# zdoks.net
KiCad netlist of a schematic drawn in Altium Designer
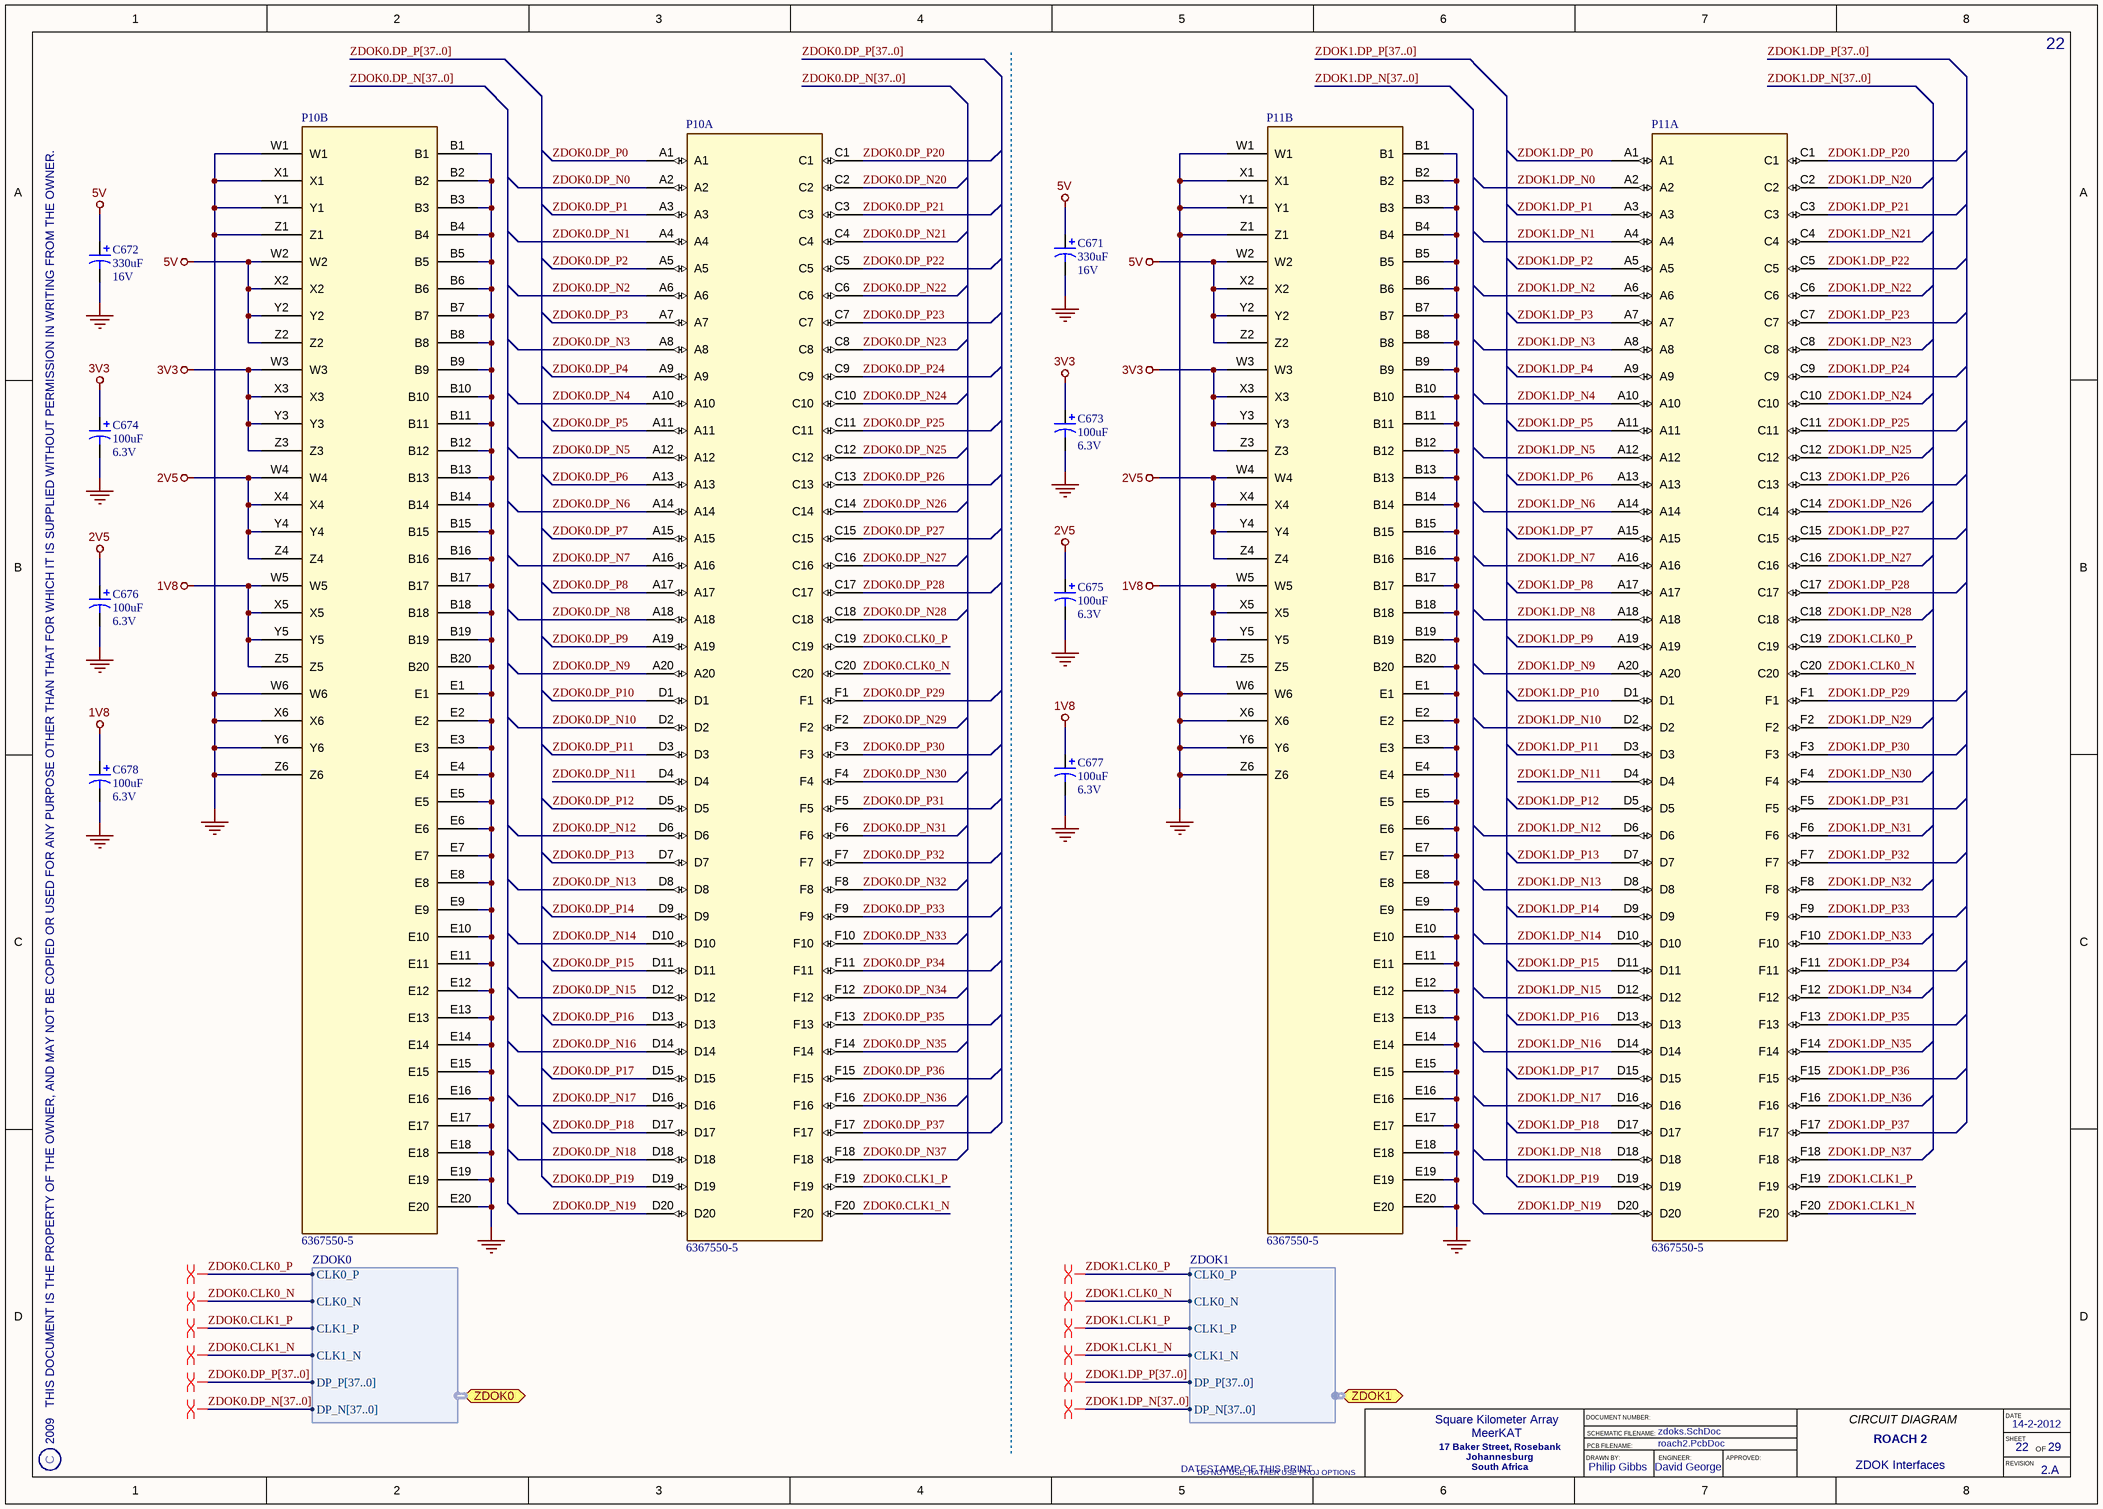
[diagram p0: zdoks.SchDoc]

(export (version "E")
  (design (tool "Eeschema 10.0.6"))
  (components
    (comp (ref "C671")
      (value "330uF")
      (footprint "CAPMP7263X380L")
      (description "330uF, Solid Tantalum Chip Capacitor")
      (fields
        (field (name "RATING") "16V")
        (field (name "MANUFACTURER") "VISHAY")
        (field (name "PARTNUM") "594D337X0016R2T")
      )
      (libsource (lib "altium_db") (part "CapPol"))
    )
    (comp (ref "C672")
      (value "330uF")
      (footprint "CAPMP7263X380L")
      (description "330uF, Solid Tantalum Chip Capacitor")
      (fields
        (field (name "RATING") "16V")
        (field (name "MANUFACTURER") "VISHAY")
        (field (name "PARTNUM") "594D337X0016R2T")
      )
      (libsource (lib "altium_db") (part "CapPol"))
    )
    (comp (ref "C673")
      (value "100uF")
      (footprint "CAPMP3528X210L")
      (description "100uF, Low ESR, Tantalum Capacitor")
      (fields
        (field (name "RATING") "6.3V")
        (field (name "MANUFACTURER") "AVX")
        (field (name "PARTNUM") "TPSB107M006R0200")
      )
      (libsource (lib "altium_db") (part "CapPol"))
    )
    (comp (ref "C674")
      (value "100uF")
      (footprint "CAPMP3528X210L")
      (description "100uF, Low ESR, Tantalum Capacitor")
      (fields
        (field (name "RATING") "6.3V")
        (field (name "MANUFACTURER") "AVX")
        (field (name "PARTNUM") "TPSB107M006R0200")
      )
      (libsource (lib "altium_db") (part "CapPol"))
    )
    (comp (ref "C675")
      (value "100uF")
      (footprint "CAPMP3528X210L")
      (description "100uF, Low ESR, Tantalum Capacitor")
      (fields
        (field (name "RATING") "6.3V")
        (field (name "MANUFACTURER") "AVX")
        (field (name "PARTNUM") "TPSB107M006R0200")
      )
      (libsource (lib "altium_db") (part "CapPol"))
    )
    (comp (ref "C676")
      (value "100uF")
      (footprint "CAPMP3528X210L")
      (description "100uF, Low ESR, Tantalum Capacitor")
      (fields
        (field (name "RATING") "6.3V")
        (field (name "MANUFACTURER") "AVX")
        (field (name "PARTNUM") "TPSB107M006R0200")
      )
      (libsource (lib "altium_db") (part "CapPol"))
    )
    (comp (ref "C677")
      (value "100uF")
      (footprint "CAPMP3528X210L")
      (description "100uF, Low ESR, Tantalum Capacitor")
      (fields
        (field (name "RATING") "6.3V")
        (field (name "MANUFACTURER") "AVX")
        (field (name "PARTNUM") "TPSB107M006R0200")
      )
      (libsource (lib "altium_db") (part "CapPol"))
    )
    (comp (ref "C678")
      (value "100uF")
      (footprint "CAPMP3528X210L")
      (description "100uF, Low ESR, Tantalum Capacitor")
      (fields
        (field (name "RATING") "6.3V")
        (field (name "MANUFACTURER") "AVX")
        (field (name "PARTNUM") "TPSB107M006R0200")
      )
      (libsource (lib "altium_db") (part "CapPol"))
    )
    (comp (ref "P10")
      (value "6367550-5")
      (footprint "TYCO_6367550-5")
      (description "ZDOK+ Host Board Connector")
      (fields (field (name "PARTNUM") "6367550-5") (field (name "MANUFACTURER") "TYCO"))
      (libsource (lib "altium_db") (part "6367550A"))
    )
    (comp (ref "P11")
      (value "6367550-5")
      (footprint "TYCO_6367550-5")
      (description "ZDOK+ Host Board Connector")
      (fields (field (name "PARTNUM") "6367550-5") (field (name "MANUFACTURER") "TYCO"))
      (libsource (lib "altium_db") (part "6367550A"))
    )
  )
  (nets
    (net (code "3") (name "/ZDOK0.CLK0_N") (class "Default")
      (node (ref "P10") (pin "C20") (pinfunction "C20_C20") (pintype "bidirectional"))
    )
    (net (code "4") (name "/ZDOK0.CLK0_P") (class "Default")
      (node (ref "P10") (pin "C19") (pinfunction "C19_C19") (pintype "bidirectional"))
    )
    (net (code "5") (name "/ZDOK0.CLK1_N") (class "Default")
      (node (ref "P10") (pin "F20") (pinfunction "F20_F20") (pintype "bidirectional"))
    )
    (net (code "6") (name "/ZDOK0.CLK1_P") (class "Default")
      (node (ref "P10") (pin "F19") (pinfunction "F19_F19") (pintype "bidirectional"))
    )
    (net (code "7") (name "/ZDOK0.DP_N0") (class "Default")
      (node (ref "P10") (pin "A2") (pinfunction "A2_A2") (pintype "bidirectional"))
    )
    (net (code "8") (name "/ZDOK0.DP_N1") (class "Default")
      (node (ref "P10") (pin "A4") (pinfunction "A4_A4") (pintype "bidirectional"))
    )
    (net (code "9") (name "/ZDOK0.DP_N2") (class "Default")
      (node (ref "P10") (pin "A6") (pinfunction "A6_A6") (pintype "bidirectional"))
    )
    (net (code "10") (name "/ZDOK0.DP_N3") (class "Default")
      (node (ref "P10") (pin "A8") (pinfunction "A8_A8") (pintype "bidirectional"))
    )
    (net (code "11") (name "/ZDOK0.DP_N4") (class "Default")
      (node (ref "P10") (pin "A10") (pinfunction "A10_A10") (pintype "bidirectional"))
    )
    (net (code "12") (name "/ZDOK0.DP_N5") (class "Default")
      (node (ref "P10") (pin "A12") (pinfunction "A12_A12") (pintype "bidirectional"))
    )
    (net (code "13") (name "/ZDOK0.DP_N6") (class "Default")
      (node (ref "P10") (pin "A14") (pinfunction "A14_A14") (pintype "bidirectional"))
    )
    (net (code "14") (name "/ZDOK0.DP_N7") (class "Default")
      (node (ref "P10") (pin "A16") (pinfunction "A16_A16") (pintype "bidirectional"))
    )
    (net (code "15") (name "/ZDOK0.DP_N8") (class "Default")
      (node (ref "P10") (pin "A18") (pinfunction "A18_A18") (pintype "bidirectional"))
    )
    (net (code "16") (name "/ZDOK0.DP_N9") (class "Default")
      (node (ref "P10") (pin "A20") (pinfunction "A20_A20") (pintype "bidirectional"))
    )
    (net (code "17") (name "/ZDOK0.DP_N10") (class "Default")
      (node (ref "P10") (pin "D2") (pinfunction "D2_D2") (pintype "bidirectional"))
    )
    (net (code "18") (name "/ZDOK0.DP_N11") (class "Default")
      (node (ref "P10") (pin "D4") (pinfunction "D4_D4") (pintype "bidirectional"))
    )
    (net (code "19") (name "/ZDOK0.DP_N12") (class "Default")
      (node (ref "P10") (pin "D6") (pinfunction "D6_D6") (pintype "bidirectional"))
    )
    (net (code "20") (name "/ZDOK0.DP_N13") (class "Default")
      (node (ref "P10") (pin "D8") (pinfunction "D8_D8") (pintype "bidirectional"))
    )
    (net (code "21") (name "/ZDOK0.DP_N14") (class "Default")
      (node (ref "P10") (pin "D10") (pinfunction "D10_D10") (pintype "bidirectional"))
    )
    (net (code "22") (name "/ZDOK0.DP_N15") (class "Default")
      (node (ref "P10") (pin "D12") (pinfunction "D12_D12") (pintype "bidirectional"))
    )
    (net (code "23") (name "/ZDOK0.DP_N16") (class "Default")
      (node (ref "P10") (pin "D14") (pinfunction "D14_D14") (pintype "bidirectional"))
    )
    (net (code "24") (name "/ZDOK0.DP_N17") (class "Default")
      (node (ref "P10") (pin "D16") (pinfunction "D16_D16") (pintype "bidirectional"))
    )
    (net (code "25") (name "/ZDOK0.DP_N18") (class "Default")
      (node (ref "P10") (pin "D18") (pinfunction "D18_D18") (pintype "bidirectional"))
    )
    (net (code "26") (name "/ZDOK0.DP_N19") (class "Default")
      (node (ref "P10") (pin "D20") (pinfunction "D20_D20") (pintype "bidirectional"))
    )
    (net (code "27") (name "/ZDOK0.DP_N20") (class "Default")
      (node (ref "P10") (pin "C2") (pinfunction "C2_C2") (pintype "bidirectional"))
    )
    (net (code "28") (name "/ZDOK0.DP_N21") (class "Default")
      (node (ref "P10") (pin "C4") (pinfunction "C4_C4") (pintype "bidirectional"))
    )
    (net (code "29") (name "/ZDOK0.DP_N22") (class "Default")
      (node (ref "P10") (pin "C6") (pinfunction "C6_C6") (pintype "bidirectional"))
    )
    (net (code "30") (name "/ZDOK0.DP_N23") (class "Default")
      (node (ref "P10") (pin "C8") (pinfunction "C8_C8") (pintype "bidirectional"))
    )
    (net (code "31") (name "/ZDOK0.DP_N24") (class "Default")
      (node (ref "P10") (pin "C10") (pinfunction "C10_C10") (pintype "bidirectional"))
    )
    (net (code "32") (name "/ZDOK0.DP_N25") (class "Default")
      (node (ref "P10") (pin "C12") (pinfunction "C12_C12") (pintype "bidirectional"))
    )
    (net (code "33") (name "/ZDOK0.DP_N26") (class "Default")
      (node (ref "P10") (pin "C14") (pinfunction "C14_C14") (pintype "bidirectional"))
    )
    (net (code "34") (name "/ZDOK0.DP_N27") (class "Default")
      (node (ref "P10") (pin "C16") (pinfunction "C16_C16") (pintype "bidirectional"))
    )
    (net (code "35") (name "/ZDOK0.DP_N28") (class "Default")
      (node (ref "P10") (pin "C18") (pinfunction "C18_C18") (pintype "bidirectional"))
    )
    (net (code "36") (name "/ZDOK0.DP_N29") (class "Default")
      (node (ref "P10") (pin "F2") (pinfunction "F2_F2") (pintype "bidirectional"))
    )
    (net (code "37") (name "/ZDOK0.DP_N30") (class "Default")
      (node (ref "P10") (pin "F4") (pinfunction "F4_F4") (pintype "bidirectional"))
    )
    (net (code "38") (name "/ZDOK0.DP_N31") (class "Default")
      (node (ref "P10") (pin "F6") (pinfunction "F6_F6") (pintype "bidirectional"))
    )
    (net (code "39") (name "/ZDOK0.DP_N32") (class "Default")
      (node (ref "P10") (pin "F8") (pinfunction "F8_F8") (pintype "bidirectional"))
    )
    (net (code "40") (name "/ZDOK0.DP_N33") (class "Default")
      (node (ref "P10") (pin "F10") (pinfunction "F10_F10") (pintype "bidirectional"))
    )
    (net (code "41") (name "/ZDOK0.DP_N34") (class "Default")
      (node (ref "P10") (pin "F12") (pinfunction "F12_F12") (pintype "bidirectional"))
    )
    (net (code "42") (name "/ZDOK0.DP_N35") (class "Default")
      (node (ref "P10") (pin "F14") (pinfunction "F14_F14") (pintype "bidirectional"))
    )
    (net (code "43") (name "/ZDOK0.DP_N36") (class "Default")
      (node (ref "P10") (pin "F16") (pinfunction "F16_F16") (pintype "bidirectional"))
    )
    (net (code "44") (name "/ZDOK0.DP_N37") (class "Default")
      (node (ref "P10") (pin "F18") (pinfunction "F18_F18") (pintype "bidirectional"))
    )
    (net (code "46") (name "/ZDOK0.DP_P0") (class "Default")
      (node (ref "P10") (pin "A1") (pinfunction "A1_A1") (pintype "bidirectional"))
    )
    (net (code "47") (name "/ZDOK0.DP_P1") (class "Default")
      (node (ref "P10") (pin "A3") (pinfunction "A3_A3") (pintype "bidirectional"))
    )
    (net (code "48") (name "/ZDOK0.DP_P2") (class "Default")
      (node (ref "P10") (pin "A5") (pinfunction "A5_A5") (pintype "bidirectional"))
    )
    (net (code "49") (name "/ZDOK0.DP_P3") (class "Default")
      (node (ref "P10") (pin "A7") (pinfunction "A7_A7") (pintype "bidirectional"))
    )
    (net (code "50") (name "/ZDOK0.DP_P4") (class "Default")
      (node (ref "P10") (pin "A9") (pinfunction "A9_A9") (pintype "bidirectional"))
    )
    (net (code "51") (name "/ZDOK0.DP_P5") (class "Default")
      (node (ref "P10") (pin "A11") (pinfunction "A11_A11") (pintype "bidirectional"))
    )
    (net (code "52") (name "/ZDOK0.DP_P6") (class "Default")
      (node (ref "P10") (pin "A13") (pinfunction "A13_A13") (pintype "bidirectional"))
    )
    (net (code "53") (name "/ZDOK0.DP_P7") (class "Default")
      (node (ref "P10") (pin "A15") (pinfunction "A15_A15") (pintype "bidirectional"))
    )
    (net (code "54") (name "/ZDOK0.DP_P8") (class "Default")
      (node (ref "P10") (pin "A17") (pinfunction "A17_A17") (pintype "bidirectional"))
    )
    (net (code "55") (name "/ZDOK0.DP_P9") (class "Default")
      (node (ref "P10") (pin "A19") (pinfunction "A19_A19") (pintype "bidirectional"))
    )
    (net (code "56") (name "/ZDOK0.DP_P10") (class "Default")
      (node (ref "P10") (pin "D1") (pinfunction "D1_D1") (pintype "bidirectional"))
    )
    (net (code "57") (name "/ZDOK0.DP_P11") (class "Default")
      (node (ref "P10") (pin "D3") (pinfunction "D3_D3") (pintype "bidirectional"))
    )
    (net (code "58") (name "/ZDOK0.DP_P12") (class "Default")
      (node (ref "P10") (pin "D5") (pinfunction "D5_D5") (pintype "bidirectional"))
    )
    (net (code "59") (name "/ZDOK0.DP_P13") (class "Default")
      (node (ref "P10") (pin "D7") (pinfunction "D7_D7") (pintype "bidirectional"))
    )
    (net (code "60") (name "/ZDOK0.DP_P14") (class "Default")
      (node (ref "P10") (pin "D9") (pinfunction "D9_D9") (pintype "bidirectional"))
    )
    (net (code "61") (name "/ZDOK0.DP_P15") (class "Default")
      (node (ref "P10") (pin "D11") (pinfunction "D11_D11") (pintype "bidirectional"))
    )
    (net (code "62") (name "/ZDOK0.DP_P16") (class "Default")
      (node (ref "P10") (pin "D13") (pinfunction "D13_D13") (pintype "bidirectional"))
    )
    (net (code "63") (name "/ZDOK0.DP_P17") (class "Default")
      (node (ref "P10") (pin "D15") (pinfunction "D15_D15") (pintype "bidirectional"))
    )
    (net (code "64") (name "/ZDOK0.DP_P18") (class "Default")
      (node (ref "P10") (pin "D17") (pinfunction "D17_D17") (pintype "bidirectional"))
    )
    (net (code "65") (name "/ZDOK0.DP_P19") (class "Default")
      (node (ref "P10") (pin "D19") (pinfunction "D19_D19") (pintype "bidirectional"))
    )
    (net (code "66") (name "/ZDOK0.DP_P20") (class "Default")
      (node (ref "P10") (pin "C1") (pinfunction "C1_C1") (pintype "bidirectional"))
    )
    (net (code "67") (name "/ZDOK0.DP_P21") (class "Default")
      (node (ref "P10") (pin "C3") (pinfunction "C3_C3") (pintype "bidirectional"))
    )
    (net (code "68") (name "/ZDOK0.DP_P22") (class "Default")
      (node (ref "P10") (pin "C5") (pinfunction "C5_C5") (pintype "bidirectional"))
    )
    (net (code "69") (name "/ZDOK0.DP_P23") (class "Default")
      (node (ref "P10") (pin "C7") (pinfunction "C7_C7") (pintype "bidirectional"))
    )
    (net (code "70") (name "/ZDOK0.DP_P24") (class "Default")
      (node (ref "P10") (pin "C9") (pinfunction "C9_C9") (pintype "bidirectional"))
    )
    (net (code "71") (name "/ZDOK0.DP_P25") (class "Default")
      (node (ref "P10") (pin "C11") (pinfunction "C11_C11") (pintype "bidirectional"))
    )
    (net (code "72") (name "/ZDOK0.DP_P26") (class "Default")
      (node (ref "P10") (pin "C13") (pinfunction "C13_C13") (pintype "bidirectional"))
    )
    (net (code "73") (name "/ZDOK0.DP_P27") (class "Default")
      (node (ref "P10") (pin "C15") (pinfunction "C15_C15") (pintype "bidirectional"))
    )
    (net (code "74") (name "/ZDOK0.DP_P28") (class "Default")
      (node (ref "P10") (pin "C17") (pinfunction "C17_C17") (pintype "bidirectional"))
    )
    (net (code "75") (name "/ZDOK0.DP_P29") (class "Default")
      (node (ref "P10") (pin "F1") (pinfunction "F1_F1") (pintype "bidirectional"))
    )
    (net (code "76") (name "/ZDOK0.DP_P30") (class "Default")
      (node (ref "P10") (pin "F3") (pinfunction "F3_F3") (pintype "bidirectional"))
    )
    (net (code "77") (name "/ZDOK0.DP_P31") (class "Default")
      (node (ref "P10") (pin "F5") (pinfunction "F5_F5") (pintype "bidirectional"))
    )
    (net (code "78") (name "/ZDOK0.DP_P32") (class "Default")
      (node (ref "P10") (pin "F7") (pinfunction "F7_F7") (pintype "bidirectional"))
    )
    (net (code "79") (name "/ZDOK0.DP_P33") (class "Default")
      (node (ref "P10") (pin "F9") (pinfunction "F9_F9") (pintype "bidirectional"))
    )
    (net (code "80") (name "/ZDOK0.DP_P34") (class "Default")
      (node (ref "P10") (pin "F11") (pinfunction "F11_F11") (pintype "bidirectional"))
    )
    (net (code "81") (name "/ZDOK0.DP_P35") (class "Default")
      (node (ref "P10") (pin "F13") (pinfunction "F13_F13") (pintype "bidirectional"))
    )
    (net (code "82") (name "/ZDOK0.DP_P36") (class "Default")
      (node (ref "P10") (pin "F15") (pinfunction "F15_F15") (pintype "bidirectional"))
    )
    (net (code "83") (name "/ZDOK0.DP_P37") (class "Default")
      (node (ref "P10") (pin "F17") (pinfunction "F17_F17") (pintype "bidirectional"))
    )
    (net (code "85") (name "/ZDOK1.CLK0_N") (class "Default")
      (node (ref "P11") (pin "C20") (pinfunction "C20_C20") (pintype "bidirectional"))
    )
    (net (code "86") (name "/ZDOK1.CLK0_P") (class "Default")
      (node (ref "P11") (pin "C19") (pinfunction "C19_C19") (pintype "bidirectional"))
    )
    (net (code "87") (name "/ZDOK1.CLK1_N") (class "Default")
      (node (ref "P11") (pin "F20") (pinfunction "F20_F20") (pintype "bidirectional"))
    )
    (net (code "88") (name "/ZDOK1.CLK1_P") (class "Default")
      (node (ref "P11") (pin "F19") (pinfunction "F19_F19") (pintype "bidirectional"))
    )
    (net (code "89") (name "/ZDOK1.DP_N0") (class "Default")
      (node (ref "P11") (pin "A2") (pinfunction "A2_A2") (pintype "bidirectional"))
    )
    (net (code "90") (name "/ZDOK1.DP_N1") (class "Default")
      (node (ref "P11") (pin "A4") (pinfunction "A4_A4") (pintype "bidirectional"))
    )
    (net (code "91") (name "/ZDOK1.DP_N2") (class "Default")
      (node (ref "P11") (pin "A6") (pinfunction "A6_A6") (pintype "bidirectional"))
    )
    (net (code "92") (name "/ZDOK1.DP_N3") (class "Default")
      (node (ref "P11") (pin "A8") (pinfunction "A8_A8") (pintype "bidirectional"))
    )
    (net (code "93") (name "/ZDOK1.DP_N4") (class "Default")
      (node (ref "P11") (pin "A10") (pinfunction "A10_A10") (pintype "bidirectional"))
    )
    (net (code "94") (name "/ZDOK1.DP_N5") (class "Default")
      (node (ref "P11") (pin "A12") (pinfunction "A12_A12") (pintype "bidirectional"))
    )
    (net (code "95") (name "/ZDOK1.DP_N6") (class "Default")
      (node (ref "P11") (pin "A14") (pinfunction "A14_A14") (pintype "bidirectional"))
    )
    (net (code "96") (name "/ZDOK1.DP_N7") (class "Default")
      (node (ref "P11") (pin "A16") (pinfunction "A16_A16") (pintype "bidirectional"))
    )
    (net (code "97") (name "/ZDOK1.DP_N8") (class "Default")
      (node (ref "P11") (pin "A18") (pinfunction "A18_A18") (pintype "bidirectional"))
    )
    (net (code "98") (name "/ZDOK1.DP_N9") (class "Default")
      (node (ref "P11") (pin "A20") (pinfunction "A20_A20") (pintype "bidirectional"))
    )
    (net (code "99") (name "/ZDOK1.DP_N10") (class "Default")
      (node (ref "P11") (pin "D2") (pinfunction "D2_D2") (pintype "bidirectional"))
    )
    (net (code "100") (name "/ZDOK1.DP_N11") (class "Default")
      (node (ref "P11") (pin "D4") (pinfunction "D4_D4") (pintype "bidirectional"))
    )
    (net (code "101") (name "/ZDOK1.DP_N12") (class "Default")
      (node (ref "P11") (pin "D6") (pinfunction "D6_D6") (pintype "bidirectional"))
    )
    (net (code "102") (name "/ZDOK1.DP_N13") (class "Default")
      (node (ref "P11") (pin "D8") (pinfunction "D8_D8") (pintype "bidirectional"))
    )
    (net (code "103") (name "/ZDOK1.DP_N14") (class "Default")
      (node (ref "P11") (pin "D10") (pinfunction "D10_D10") (pintype "bidirectional"))
    )
    (net (code "104") (name "/ZDOK1.DP_N15") (class "Default")
      (node (ref "P11") (pin "D12") (pinfunction "D12_D12") (pintype "bidirectional"))
    )
    (net (code "105") (name "/ZDOK1.DP_N16") (class "Default")
      (node (ref "P11") (pin "D14") (pinfunction "D14_D14") (pintype "bidirectional"))
    )
    (net (code "106") (name "/ZDOK1.DP_N17") (class "Default")
      (node (ref "P11") (pin "D16") (pinfunction "D16_D16") (pintype "bidirectional"))
    )
    (net (code "107") (name "/ZDOK1.DP_N18") (class "Default")
      (node (ref "P11") (pin "D18") (pinfunction "D18_D18") (pintype "bidirectional"))
    )
    (net (code "108") (name "/ZDOK1.DP_N19") (class "Default")
      (node (ref "P11") (pin "D20") (pinfunction "D20_D20") (pintype "bidirectional"))
    )
    (net (code "109") (name "/ZDOK1.DP_N20") (class "Default")
      (node (ref "P11") (pin "C2") (pinfunction "C2_C2") (pintype "bidirectional"))
    )
    (net (code "110") (name "/ZDOK1.DP_N21") (class "Default")
      (node (ref "P11") (pin "C4") (pinfunction "C4_C4") (pintype "bidirectional"))
    )
    (net (code "111") (name "/ZDOK1.DP_N22") (class "Default")
      (node (ref "P11") (pin "C6") (pinfunction "C6_C6") (pintype "bidirectional"))
    )
    (net (code "112") (name "/ZDOK1.DP_N23") (class "Default")
      (node (ref "P11") (pin "C8") (pinfunction "C8_C8") (pintype "bidirectional"))
    )
    (net (code "113") (name "/ZDOK1.DP_N24") (class "Default")
      (node (ref "P11") (pin "C10") (pinfunction "C10_C10") (pintype "bidirectional"))
    )
    (net (code "114") (name "/ZDOK1.DP_N25") (class "Default")
      (node (ref "P11") (pin "C12") (pinfunction "C12_C12") (pintype "bidirectional"))
    )
    (net (code "115") (name "/ZDOK1.DP_N26") (class "Default")
      (node (ref "P11") (pin "C14") (pinfunction "C14_C14") (pintype "bidirectional"))
    )
    (net (code "116") (name "/ZDOK1.DP_N27") (class "Default")
      (node (ref "P11") (pin "C16") (pinfunction "C16_C16") (pintype "bidirectional"))
    )
    (net (code "117") (name "/ZDOK1.DP_N28") (class "Default")
      (node (ref "P11") (pin "C18") (pinfunction "C18_C18") (pintype "bidirectional"))
    )
    (net (code "118") (name "/ZDOK1.DP_N29") (class "Default")
      (node (ref "P11") (pin "F2") (pinfunction "F2_F2") (pintype "bidirectional"))
    )
    (net (code "119") (name "/ZDOK1.DP_N30") (class "Default")
      (node (ref "P11") (pin "F4") (pinfunction "F4_F4") (pintype "bidirectional"))
    )
    (net (code "120") (name "/ZDOK1.DP_N31") (class "Default")
      (node (ref "P11") (pin "F6") (pinfunction "F6_F6") (pintype "bidirectional"))
    )
    (net (code "121") (name "/ZDOK1.DP_N32") (class "Default")
      (node (ref "P11") (pin "F8") (pinfunction "F8_F8") (pintype "bidirectional"))
    )
    (net (code "122") (name "/ZDOK1.DP_N33") (class "Default")
      (node (ref "P11") (pin "F10") (pinfunction "F10_F10") (pintype "bidirectional"))
    )
    (net (code "123") (name "/ZDOK1.DP_N34") (class "Default")
      (node (ref "P11") (pin "F12") (pinfunction "F12_F12") (pintype "bidirectional"))
    )
    (net (code "124") (name "/ZDOK1.DP_N35") (class "Default")
      (node (ref "P11") (pin "F14") (pinfunction "F14_F14") (pintype "bidirectional"))
    )
    (net (code "125") (name "/ZDOK1.DP_N36") (class "Default")
      (node (ref "P11") (pin "F16") (pinfunction "F16_F16") (pintype "bidirectional"))
    )
    (net (code "126") (name "/ZDOK1.DP_N37") (class "Default")
      (node (ref "P11") (pin "F18") (pinfunction "F18_F18") (pintype "bidirectional"))
    )
    (net (code "128") (name "/ZDOK1.DP_P0") (class "Default")
      (node (ref "P11") (pin "A1") (pinfunction "A1_A1") (pintype "bidirectional"))
    )
    (net (code "129") (name "/ZDOK1.DP_P1") (class "Default")
      (node (ref "P11") (pin "A3") (pinfunction "A3_A3") (pintype "bidirectional"))
    )
    (net (code "130") (name "/ZDOK1.DP_P2") (class "Default")
      (node (ref "P11") (pin "A5") (pinfunction "A5_A5") (pintype "bidirectional"))
    )
    (net (code "131") (name "/ZDOK1.DP_P3") (class "Default")
      (node (ref "P11") (pin "A7") (pinfunction "A7_A7") (pintype "bidirectional"))
    )
    (net (code "132") (name "/ZDOK1.DP_P4") (class "Default")
      (node (ref "P11") (pin "A9") (pinfunction "A9_A9") (pintype "bidirectional"))
    )
    (net (code "133") (name "/ZDOK1.DP_P5") (class "Default")
      (node (ref "P11") (pin "A11") (pinfunction "A11_A11") (pintype "bidirectional"))
    )
    (net (code "134") (name "/ZDOK1.DP_P6") (class "Default")
      (node (ref "P11") (pin "A13") (pinfunction "A13_A13") (pintype "bidirectional"))
    )
    (net (code "135") (name "/ZDOK1.DP_P7") (class "Default")
      (node (ref "P11") (pin "A15") (pinfunction "A15_A15") (pintype "bidirectional"))
    )
    (net (code "136") (name "/ZDOK1.DP_P8") (class "Default")
      (node (ref "P11") (pin "A17") (pinfunction "A17_A17") (pintype "bidirectional"))
    )
    (net (code "137") (name "/ZDOK1.DP_P9") (class "Default")
      (node (ref "P11") (pin "A19") (pinfunction "A19_A19") (pintype "bidirectional"))
    )
    (net (code "138") (name "/ZDOK1.DP_P10") (class "Default")
      (node (ref "P11") (pin "D1") (pinfunction "D1_D1") (pintype "bidirectional"))
    )
    (net (code "139") (name "/ZDOK1.DP_P11") (class "Default")
      (node (ref "P11") (pin "D3") (pinfunction "D3_D3") (pintype "bidirectional"))
    )
    (net (code "140") (name "/ZDOK1.DP_P12") (class "Default")
      (node (ref "P11") (pin "D5") (pinfunction "D5_D5") (pintype "bidirectional"))
    )
    (net (code "141") (name "/ZDOK1.DP_P13") (class "Default")
      (node (ref "P11") (pin "D7") (pinfunction "D7_D7") (pintype "bidirectional"))
    )
    (net (code "142") (name "/ZDOK1.DP_P14") (class "Default")
      (node (ref "P11") (pin "D9") (pinfunction "D9_D9") (pintype "bidirectional"))
    )
    (net (code "143") (name "/ZDOK1.DP_P15") (class "Default")
      (node (ref "P11") (pin "D11") (pinfunction "D11_D11") (pintype "bidirectional"))
    )
    (net (code "144") (name "/ZDOK1.DP_P16") (class "Default")
      (node (ref "P11") (pin "D13") (pinfunction "D13_D13") (pintype "bidirectional"))
    )
    (net (code "145") (name "/ZDOK1.DP_P17") (class "Default")
      (node (ref "P11") (pin "D15") (pinfunction "D15_D15") (pintype "bidirectional"))
    )
    (net (code "146") (name "/ZDOK1.DP_P18") (class "Default")
      (node (ref "P11") (pin "D17") (pinfunction "D17_D17") (pintype "bidirectional"))
    )
    (net (code "147") (name "/ZDOK1.DP_P19") (class "Default")
      (node (ref "P11") (pin "D19") (pinfunction "D19_D19") (pintype "bidirectional"))
    )
    (net (code "148") (name "/ZDOK1.DP_P20") (class "Default")
      (node (ref "P11") (pin "C1") (pinfunction "C1_C1") (pintype "bidirectional"))
    )
    (net (code "149") (name "/ZDOK1.DP_P21") (class "Default")
      (node (ref "P11") (pin "C3") (pinfunction "C3_C3") (pintype "bidirectional"))
    )
    (net (code "150") (name "/ZDOK1.DP_P22") (class "Default")
      (node (ref "P11") (pin "C5") (pinfunction "C5_C5") (pintype "bidirectional"))
    )
    (net (code "151") (name "/ZDOK1.DP_P23") (class "Default")
      (node (ref "P11") (pin "C7") (pinfunction "C7_C7") (pintype "bidirectional"))
    )
    (net (code "152") (name "/ZDOK1.DP_P24") (class "Default")
      (node (ref "P11") (pin "C9") (pinfunction "C9_C9") (pintype "bidirectional"))
    )
    (net (code "153") (name "/ZDOK1.DP_P25") (class "Default")
      (node (ref "P11") (pin "C11") (pinfunction "C11_C11") (pintype "bidirectional"))
    )
    (net (code "154") (name "/ZDOK1.DP_P26") (class "Default")
      (node (ref "P11") (pin "C13") (pinfunction "C13_C13") (pintype "bidirectional"))
    )
    (net (code "155") (name "/ZDOK1.DP_P27") (class "Default")
      (node (ref "P11") (pin "C15") (pinfunction "C15_C15") (pintype "bidirectional"))
    )
    (net (code "156") (name "/ZDOK1.DP_P28") (class "Default")
      (node (ref "P11") (pin "C17") (pinfunction "C17_C17") (pintype "bidirectional"))
    )
    (net (code "157") (name "/ZDOK1.DP_P29") (class "Default")
      (node (ref "P11") (pin "F1") (pinfunction "F1_F1") (pintype "bidirectional"))
    )
    (net (code "158") (name "/ZDOK1.DP_P30") (class "Default")
      (node (ref "P11") (pin "F3") (pinfunction "F3_F3") (pintype "bidirectional"))
    )
    (net (code "159") (name "/ZDOK1.DP_P31") (class "Default")
      (node (ref "P11") (pin "F5") (pinfunction "F5_F5") (pintype "bidirectional"))
    )
    (net (code "160") (name "/ZDOK1.DP_P32") (class "Default")
      (node (ref "P11") (pin "F7") (pinfunction "F7_F7") (pintype "bidirectional"))
    )
    (net (code "161") (name "/ZDOK1.DP_P33") (class "Default")
      (node (ref "P11") (pin "F9") (pinfunction "F9_F9") (pintype "bidirectional"))
    )
    (net (code "162") (name "/ZDOK1.DP_P34") (class "Default")
      (node (ref "P11") (pin "F11") (pinfunction "F11_F11") (pintype "bidirectional"))
    )
    (net (code "163") (name "/ZDOK1.DP_P35") (class "Default")
      (node (ref "P11") (pin "F13") (pinfunction "F13_F13") (pintype "bidirectional"))
    )
    (net (code "164") (name "/ZDOK1.DP_P36") (class "Default")
      (node (ref "P11") (pin "F15") (pinfunction "F15_F15") (pintype "bidirectional"))
    )
    (net (code "165") (name "/ZDOK1.DP_P37") (class "Default")
      (node (ref "P11") (pin "F17") (pinfunction "F17_F17") (pintype "bidirectional"))
    )
    (net (code "170") (name "1V8") (class "Default")
      (node (ref "C677") (pin "1") (pinfunction "1_1") (pintype "passive"))
      (node (ref "C678") (pin "1") (pinfunction "1_1") (pintype "passive"))
      (node (ref "P10") (pin "W5") (pinfunction "W5_W5") (pintype "power_in"))
      (node (ref "P10") (pin "X5") (pinfunction "X5_X5") (pintype "power_in"))
      (node (ref "P10") (pin "Y5") (pinfunction "Y5_Y5") (pintype "power_in"))
      (node (ref "P10") (pin "Z5") (pinfunction "Z5_Z5") (pintype "power_in"))
      (node (ref "P11") (pin "W5") (pinfunction "W5_W5") (pintype "power_in"))
      (node (ref "P11") (pin "X5") (pinfunction "X5_X5") (pintype "power_in"))
      (node (ref "P11") (pin "Y5") (pinfunction "Y5_Y5") (pintype "power_in"))
      (node (ref "P11") (pin "Z5") (pinfunction "Z5_Z5") (pintype "power_in"))
    )
    (net (code "171") (name "2V5") (class "Default")
      (node (ref "C675") (pin "1") (pinfunction "1_1") (pintype "passive"))
      (node (ref "C676") (pin "1") (pinfunction "1_1") (pintype "passive"))
      (node (ref "P10") (pin "W4") (pinfunction "W4_W4") (pintype "power_in"))
      (node (ref "P10") (pin "X4") (pinfunction "X4_X4") (pintype "power_in"))
      (node (ref "P10") (pin "Y4") (pinfunction "Y4_Y4") (pintype "power_in"))
      (node (ref "P10") (pin "Z4") (pinfunction "Z4_Z4") (pintype "power_in"))
      (node (ref "P11") (pin "W4") (pinfunction "W4_W4") (pintype "power_in"))
      (node (ref "P11") (pin "X4") (pinfunction "X4_X4") (pintype "power_in"))
      (node (ref "P11") (pin "Y4") (pinfunction "Y4_Y4") (pintype "power_in"))
      (node (ref "P11") (pin "Z4") (pinfunction "Z4_Z4") (pintype "power_in"))
    )
    (net (code "172") (name "3V3") (class "Default")
      (node (ref "C673") (pin "1") (pinfunction "1_1") (pintype "passive"))
      (node (ref "C674") (pin "1") (pinfunction "1_1") (pintype "passive"))
      (node (ref "P10") (pin "W3") (pinfunction "W3_W3") (pintype "power_in"))
      (node (ref "P10") (pin "X3") (pinfunction "X3_X3") (pintype "power_in"))
      (node (ref "P10") (pin "Y3") (pinfunction "Y3_Y3") (pintype "power_in"))
      (node (ref "P10") (pin "Z3") (pinfunction "Z3_Z3") (pintype "power_in"))
      (node (ref "P11") (pin "W3") (pinfunction "W3_W3") (pintype "power_in"))
      (node (ref "P11") (pin "X3") (pinfunction "X3_X3") (pintype "power_in"))
      (node (ref "P11") (pin "Y3") (pinfunction "Y3_Y3") (pintype "power_in"))
      (node (ref "P11") (pin "Z3") (pinfunction "Z3_Z3") (pintype "power_in"))
    )
    (net (code "173") (name "5V") (class "Default")
      (node (ref "C671") (pin "1") (pinfunction "1_1") (pintype "passive"))
      (node (ref "C672") (pin "1") (pinfunction "1_1") (pintype "passive"))
      (node (ref "P10") (pin "W2") (pinfunction "W2_W2") (pintype "power_in"))
      (node (ref "P10") (pin "X2") (pinfunction "X2_X2") (pintype "power_in"))
      (node (ref "P10") (pin "Y2") (pinfunction "Y2_Y2") (pintype "power_in"))
      (node (ref "P10") (pin "Z2") (pinfunction "Z2_Z2") (pintype "power_in"))
      (node (ref "P11") (pin "W2") (pinfunction "W2_W2") (pintype "power_in"))
      (node (ref "P11") (pin "X2") (pinfunction "X2_X2") (pintype "power_in"))
      (node (ref "P11") (pin "Y2") (pinfunction "Y2_Y2") (pintype "power_in"))
      (node (ref "P11") (pin "Z2") (pinfunction "Z2_Z2") (pintype "power_in"))
    )
    (net (code "174") (name "GND") (class "Default")
      (node (ref "C671") (pin "2") (pinfunction "2_2") (pintype "passive"))
      (node (ref "C672") (pin "2") (pinfunction "2_2") (pintype "passive"))
      (node (ref "C673") (pin "2") (pinfunction "2_2") (pintype "passive"))
      (node (ref "C674") (pin "2") (pinfunction "2_2") (pintype "passive"))
      (node (ref "C675") (pin "2") (pinfunction "2_2") (pintype "passive"))
      (node (ref "C676") (pin "2") (pinfunction "2_2") (pintype "passive"))
      (node (ref "C677") (pin "2") (pinfunction "2_2") (pintype "passive"))
      (node (ref "C678") (pin "2") (pinfunction "2_2") (pintype "passive"))
      (node (ref "P10") (pin "B1") (pinfunction "B1_B1") (pintype "power_in"))
      (node (ref "P10") (pin "B10") (pinfunction "B10_B10") (pintype "power_in"))
      (node (ref "P10") (pin "B11") (pinfunction "B11_B11") (pintype "power_in"))
      (node (ref "P10") (pin "B12") (pinfunction "B12_B12") (pintype "power_in"))
      (node (ref "P10") (pin "B13") (pinfunction "B13_B13") (pintype "power_in"))
      (node (ref "P10") (pin "B14") (pinfunction "B14_B14") (pintype "power_in"))
      (node (ref "P10") (pin "B15") (pinfunction "B15_B15") (pintype "power_in"))
      (node (ref "P10") (pin "B16") (pinfunction "B16_B16") (pintype "power_in"))
      (node (ref "P10") (pin "B17") (pinfunction "B17_B17") (pintype "power_in"))
      (node (ref "P10") (pin "B18") (pinfunction "B18_B18") (pintype "power_in"))
      (node (ref "P10") (pin "B19") (pinfunction "B19_B19") (pintype "power_in"))
      (node (ref "P10") (pin "B2") (pinfunction "B2_B2") (pintype "power_in"))
      (node (ref "P10") (pin "B20") (pinfunction "B20_B20") (pintype "power_in"))
      (node (ref "P10") (pin "B3") (pinfunction "B3_B3") (pintype "power_in"))
      (node (ref "P10") (pin "B4") (pinfunction "B4_B4") (pintype "power_in"))
      (node (ref "P10") (pin "B5") (pinfunction "B5_B5") (pintype "power_in"))
      (node (ref "P10") (pin "B6") (pinfunction "B6_B6") (pintype "power_in"))
      (node (ref "P10") (pin "B7") (pinfunction "B7_B7") (pintype "power_in"))
      (node (ref "P10") (pin "B8") (pinfunction "B8_B8") (pintype "power_in"))
      (node (ref "P10") (pin "B9") (pinfunction "B9_B9") (pintype "power_in"))
      (node (ref "P10") (pin "E1") (pinfunction "E1_E1") (pintype "power_in"))
      (node (ref "P10") (pin "E10") (pinfunction "E10_E10") (pintype "power_in"))
      (node (ref "P10") (pin "E11") (pinfunction "E11_E11") (pintype "power_in"))
      (node (ref "P10") (pin "E12") (pinfunction "E12_E12") (pintype "power_in"))
      (node (ref "P10") (pin "E13") (pinfunction "E13_E13") (pintype "power_in"))
      (node (ref "P10") (pin "E14") (pinfunction "E14_E14") (pintype "power_in"))
      (node (ref "P10") (pin "E15") (pinfunction "E15_E15") (pintype "power_in"))
      (node (ref "P10") (pin "E16") (pinfunction "E16_E16") (pintype "power_in"))
      (node (ref "P10") (pin "E17") (pinfunction "E17_E17") (pintype "power_in"))
      (node (ref "P10") (pin "E18") (pinfunction "E18_E18") (pintype "power_in"))
      (node (ref "P10") (pin "E19") (pinfunction "E19_E19") (pintype "power_in"))
      (node (ref "P10") (pin "E2") (pinfunction "E2_E2") (pintype "power_in"))
      (node (ref "P10") (pin "E20") (pinfunction "E20_E20") (pintype "power_in"))
      (node (ref "P10") (pin "E3") (pinfunction "E3_E3") (pintype "power_in"))
      (node (ref "P10") (pin "E4") (pinfunction "E4_E4") (pintype "power_in"))
      (node (ref "P10") (pin "E5") (pinfunction "E5_E5") (pintype "power_in"))
      (node (ref "P10") (pin "E6") (pinfunction "E6_E6") (pintype "power_in"))
      (node (ref "P10") (pin "E7") (pinfunction "E7_E7") (pintype "power_in"))
      (node (ref "P10") (pin "E8") (pinfunction "E8_E8") (pintype "power_in"))
      (node (ref "P10") (pin "E9") (pinfunction "E9_E9") (pintype "power_in"))
      (node (ref "P10") (pin "W1") (pinfunction "W1_W1") (pintype "power_in"))
      (node (ref "P10") (pin "W6") (pinfunction "W6_W6") (pintype "power_in"))
      (node (ref "P10") (pin "X1") (pinfunction "X1_X1") (pintype "power_in"))
      (node (ref "P10") (pin "X6") (pinfunction "X6_X6") (pintype "power_in"))
      (node (ref "P10") (pin "Y1") (pinfunction "Y1_Y1") (pintype "power_in"))
      (node (ref "P10") (pin "Y6") (pinfunction "Y6_Y6") (pintype "power_in"))
      (node (ref "P10") (pin "Z1") (pinfunction "Z1_Z1") (pintype "power_in"))
      (node (ref "P10") (pin "Z6") (pinfunction "Z6_Z6") (pintype "power_in"))
      (node (ref "P11") (pin "B1") (pinfunction "B1_B1") (pintype "power_in"))
      (node (ref "P11") (pin "B10") (pinfunction "B10_B10") (pintype "power_in"))
      (node (ref "P11") (pin "B11") (pinfunction "B11_B11") (pintype "power_in"))
      (node (ref "P11") (pin "B12") (pinfunction "B12_B12") (pintype "power_in"))
      (node (ref "P11") (pin "B13") (pinfunction "B13_B13") (pintype "power_in"))
      (node (ref "P11") (pin "B14") (pinfunction "B14_B14") (pintype "power_in"))
      (node (ref "P11") (pin "B15") (pinfunction "B15_B15") (pintype "power_in"))
      (node (ref "P11") (pin "B16") (pinfunction "B16_B16") (pintype "power_in"))
      (node (ref "P11") (pin "B17") (pinfunction "B17_B17") (pintype "power_in"))
      (node (ref "P11") (pin "B18") (pinfunction "B18_B18") (pintype "power_in"))
      (node (ref "P11") (pin "B19") (pinfunction "B19_B19") (pintype "power_in"))
      (node (ref "P11") (pin "B2") (pinfunction "B2_B2") (pintype "power_in"))
      (node (ref "P11") (pin "B20") (pinfunction "B20_B20") (pintype "power_in"))
      (node (ref "P11") (pin "B3") (pinfunction "B3_B3") (pintype "power_in"))
      (node (ref "P11") (pin "B4") (pinfunction "B4_B4") (pintype "power_in"))
      (node (ref "P11") (pin "B5") (pinfunction "B5_B5") (pintype "power_in"))
      (node (ref "P11") (pin "B6") (pinfunction "B6_B6") (pintype "power_in"))
      (node (ref "P11") (pin "B7") (pinfunction "B7_B7") (pintype "power_in"))
      (node (ref "P11") (pin "B8") (pinfunction "B8_B8") (pintype "power_in"))
      (node (ref "P11") (pin "B9") (pinfunction "B9_B9") (pintype "power_in"))
      (node (ref "P11") (pin "E1") (pinfunction "E1_E1") (pintype "power_in"))
      (node (ref "P11") (pin "E10") (pinfunction "E10_E10") (pintype "power_in"))
      (node (ref "P11") (pin "E11") (pinfunction "E11_E11") (pintype "power_in"))
      (node (ref "P11") (pin "E12") (pinfunction "E12_E12") (pintype "power_in"))
      (node (ref "P11") (pin "E13") (pinfunction "E13_E13") (pintype "power_in"))
      (node (ref "P11") (pin "E14") (pinfunction "E14_E14") (pintype "power_in"))
      (node (ref "P11") (pin "E15") (pinfunction "E15_E15") (pintype "power_in"))
      (node (ref "P11") (pin "E16") (pinfunction "E16_E16") (pintype "power_in"))
      (node (ref "P11") (pin "E17") (pinfunction "E17_E17") (pintype "power_in"))
      (node (ref "P11") (pin "E18") (pinfunction "E18_E18") (pintype "power_in"))
      (node (ref "P11") (pin "E19") (pinfunction "E19_E19") (pintype "power_in"))
      (node (ref "P11") (pin "E2") (pinfunction "E2_E2") (pintype "power_in"))
      (node (ref "P11") (pin "E20") (pinfunction "E20_E20") (pintype "power_in"))
      (node (ref "P11") (pin "E3") (pinfunction "E3_E3") (pintype "power_in"))
      (node (ref "P11") (pin "E4") (pinfunction "E4_E4") (pintype "power_in"))
      (node (ref "P11") (pin "E5") (pinfunction "E5_E5") (pintype "power_in"))
      (node (ref "P11") (pin "E6") (pinfunction "E6_E6") (pintype "power_in"))
      (node (ref "P11") (pin "E7") (pinfunction "E7_E7") (pintype "power_in"))
      (node (ref "P11") (pin "E8") (pinfunction "E8_E8") (pintype "power_in"))
      (node (ref "P11") (pin "E9") (pinfunction "E9_E9") (pintype "power_in"))
      (node (ref "P11") (pin "W1") (pinfunction "W1_W1") (pintype "power_in"))
      (node (ref "P11") (pin "W6") (pinfunction "W6_W6") (pintype "power_in"))
      (node (ref "P11") (pin "X1") (pinfunction "X1_X1") (pintype "power_in"))
      (node (ref "P11") (pin "X6") (pinfunction "X6_X6") (pintype "power_in"))
      (node (ref "P11") (pin "Y1") (pinfunction "Y1_Y1") (pintype "power_in"))
      (node (ref "P11") (pin "Y6") (pinfunction "Y6_Y6") (pintype "power_in"))
      (node (ref "P11") (pin "Z1") (pinfunction "Z1_Z1") (pintype "power_in"))
      (node (ref "P11") (pin "Z6") (pinfunction "Z6_Z6") (pintype "power_in"))
    )
  )
)
